# LPC_Female_FMC.net
KiCad netlist of a schematic drawn in Altium Designer
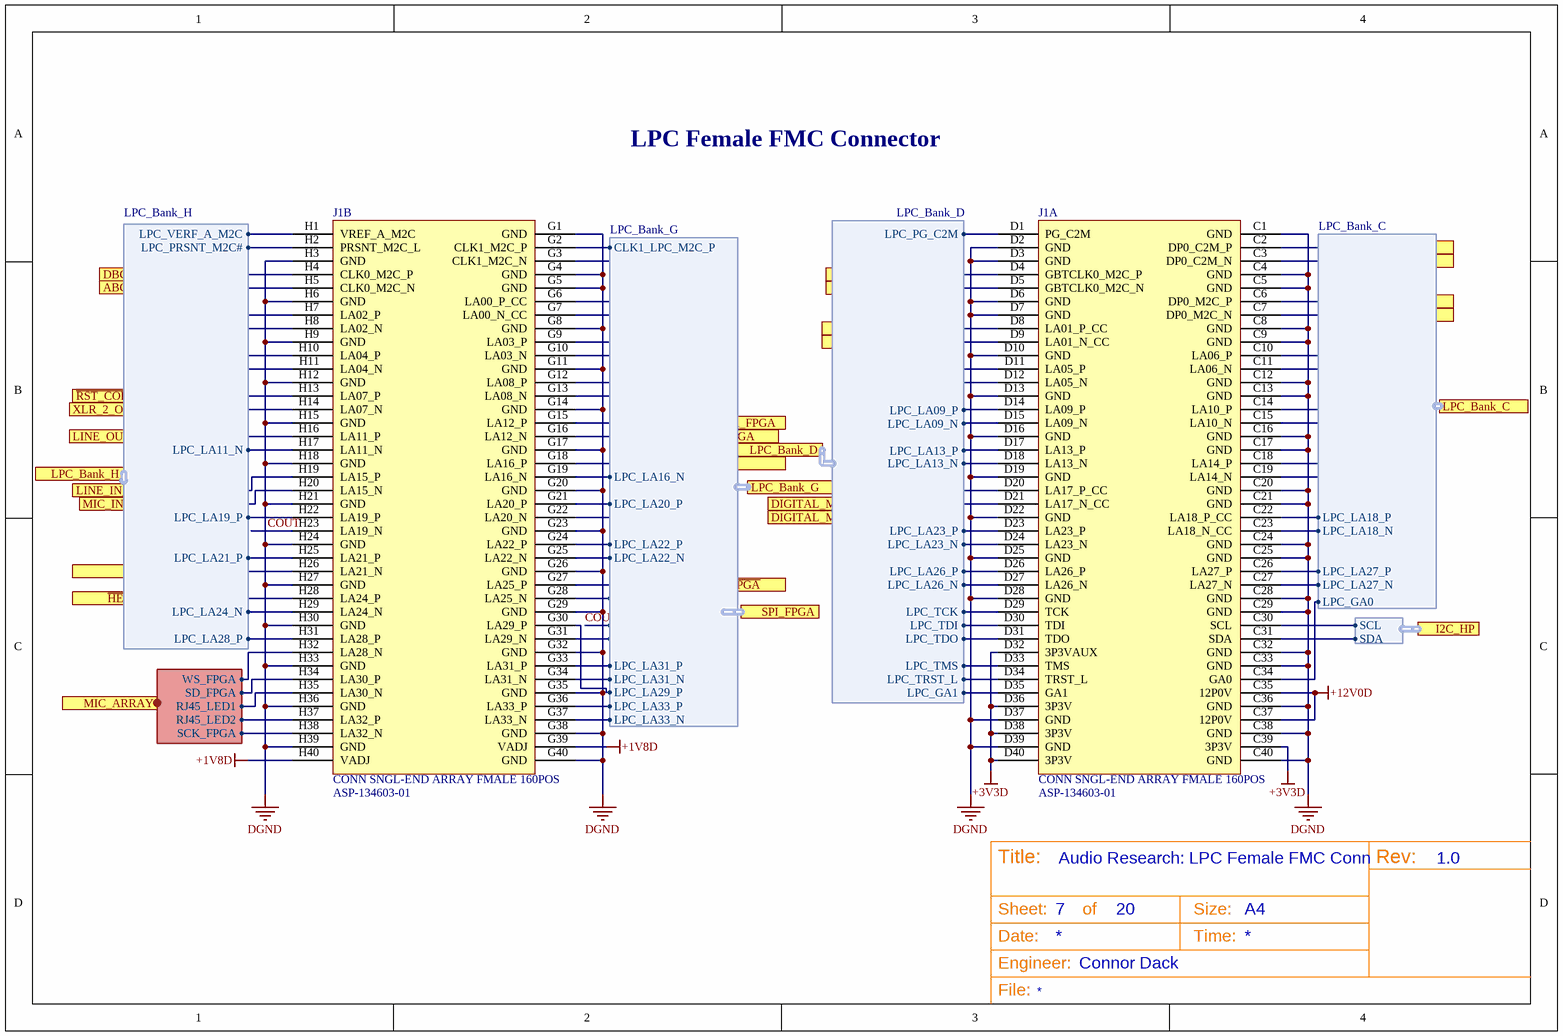
[diagram p0: LPC_Female_FMC.SchDoc]

(export (version "E")
  (design (tool "Eeschema 10.0.6"))
  (components
    (comp (ref "J1")
      (value "CONN SNGL-END ARRAY FMALE 160POS")
      (footprint "ASP-134603-01")
      (description "Low Pin Count Female FPGA Mezzanine Card Connector")
      (fields
        (field (name "MANUFACTURER") "Samtec")
        (field (name "MANUFACTURER PART NUMBER") "ASP-134603-01")
      )
      (libsource (lib "Schematic_Components_CD") (part "ASP-134603-01"))
    )
  )
  (nets
    (net (code "9") (name "+1V8D") (class "Default")
      (node (ref "J1") (pin "G39") (pinfunction "VADJ_G39") (pintype "power_in"))
      (node (ref "J1") (pin "H40") (pinfunction "VADJ_H40") (pintype "power_in"))
    )
    (net (code "10") (name "+3V3D") (class "Default")
      (node (ref "J1") (pin "C39") (pinfunction "3P3V_C39") (pintype "power_in"))
      (node (ref "J1") (pin "D32") (pinfunction "3P3VAUX_D32") (pintype "power_in"))
      (node (ref "J1") (pin "D36") (pinfunction "3P3V_D36") (pintype "power_in"))
      (node (ref "J1") (pin "D38") (pinfunction "3P3V_D38") (pintype "power_in"))
      (node (ref "J1") (pin "D40") (pinfunction "3P3V_D40") (pintype "power_in"))
    )
    (net (code "11") (name "+12V0D") (class "Default")
      (node (ref "J1") (pin "C10") (pinfunction "LA06_P_C10") (pintype "passive"))
      (node (ref "J1") (pin "C11") (pinfunction "LA06_N_C11") (pintype "passive"))
      (node (ref "J1") (pin "C35") (pinfunction "12P0V_C35") (pintype "power_in"))
      (node (ref "J1") (pin "C37") (pinfunction "12P0V_C37") (pintype "power_in"))
      (node (ref "J1") (pin "D11") (pinfunction "LA05_P_D11") (pintype "passive"))
      (node (ref "J1") (pin "D12") (pinfunction "LA05_N_D12") (pintype "passive"))
      (node (ref "J1") (pin "G12") (pinfunction "LA08_P_G12") (pintype "passive"))
      (node (ref "J1") (pin "G13") (pinfunction "LA08_N_G13") (pintype "passive"))
      (node (ref "J1") (pin "H11") (pinfunction "LA04_N_H11") (pintype "passive"))
    )
    (net (code "12") (name "/ABCLK_FPGA") (class "Default")
      (node (ref "J1") (pin "H5") (pinfunction "CLK0_M2C_N_H5") (pintype "passive"))
    )
    (net (code "13") (name "/ALRCLK_FPGA") (class "Default")
      (node (ref "J1") (pin "G22") (pinfunction "LA20_N_G22") (pintype "passive"))
    )
    (net (code "14") (name "/CCLK_FPGA") (class "Default")
      (node (ref "J1") (pin "G31") (pinfunction "LA29_N_G31") (pintype "passive"))
    )
    (net (code "15") (name "/CIN_FPGA") (class "Default")
      (node (ref "J1") (pin "G28") (pinfunction "LA25_N_G28") (pintype "passive"))
    )
    (net (code "16") (name "/CLK1_LPC_M2C_P") (class "Default")
      (node (ref "J1") (pin "G2") (pinfunction "CLK1_M2C_P_G2") (pintype "passive"))
    )
    (net (code "17") (name "/CMD_DIR1") (class "Default")
      (node (ref "J1") (pin "C19") (pinfunction "LA14_N_C19") (pintype "passive"))
    )
    (net (code "18") (name "/CMD_DIR2") (class "Default")
      (node (ref "J1") (pin "C18") (pinfunction "LA14_P_C18") (pintype "passive"))
    )
    (net (code "19") (name "/COUT") (class "Default")
      (node (ref "J1") (pin "H23") (pinfunction "LA19_N_H23") (pintype "passive"))
    )
    (net (code "20") (name "/DATA_DIR1") (class "Default")
      (node (ref "J1") (pin "C15") (pinfunction "LA10_N_C15") (pintype "passive"))
    )
    (net (code "21") (name "/DATA_DIR2") (class "Default")
      (node (ref "J1") (pin "C14") (pinfunction "LA10_P_C14") (pintype "passive"))
    )
    (net (code "22") (name "/DBCLK_FPGA") (class "Default")
      (node (ref "J1") (pin "H4") (pinfunction "CLK0_M2C_P_H4") (pintype "passive"))
    )
    (net (code "23") (name "/DIGITAL_MIC_CLK") (class "Default")
      (node (ref "J1") (pin "D20") (pinfunction "LA17_P_CC_D20") (pintype "passive"))
    )
    (net (code "24") (name "/DIGITAL_MIC_DATA") (class "Default")
      (node (ref "J1") (pin "D21") (pinfunction "LA17_N_CC_D21") (pintype "passive"))
    )
    (net (code "25") (name "/DLRCLK_FPGA") (class "Default")
      (node (ref "J1") (pin "G18") (pinfunction "LA16_P_G18") (pintype "passive"))
    )
    (net (code "26") (name "/HP_OUT_DSDATA_FPGA") (class "Default")
      (node (ref "J1") (pin "G16") (pinfunction "LA12_N_G16") (pintype "passive"))
    )
    (net (code "27") (name "/LED1") (class "Default")
      (node (ref "J1") (pin "C7") (pinfunction "DP0_M2C_N_C7") (pintype "passive"))
    )
    (net (code "28") (name "/LED2") (class "Default")
      (node (ref "J1") (pin "D8") (pinfunction "LA01_P_CC_D8") (pintype "passive"))
    )
    (net (code "29") (name "/LED3") (class "Default")
      (node (ref "J1") (pin "D9") (pinfunction "LA01_N_CC_D9") (pintype "passive"))
    )
    (net (code "30") (name "/LED4") (class "Default")
      (node (ref "J1") (pin "C6") (pinfunction "DP0_M2C_P_C6") (pintype "passive"))
    )
    (net (code "31") (name "/LINE_IN_DSDATA_FPGA") (class "Default")
      (node (ref "J1") (pin "H19") (pinfunction "LA15_P_H19") (pintype "passive"))
    )
    (net (code "32") (name "/LINE_OUT_DSDATA_FPGA") (class "Default")
      (node (ref "J1") (pin "H16") (pinfunction "LA11_P_H16") (pintype "passive"))
    )
    (net (code "34") (name "/LPC_GA0") (class "Default")
      (node (ref "J1") (pin "C34") (pinfunction "GA0_C34") (pintype "passive"))
    )
    (net (code "35") (name "/LPC_GA1") (class "Default")
      (node (ref "J1") (pin "D35") (pinfunction "GA1_D35") (pintype "passive"))
    )
    (net (code "36") (name "/LPC_LA09_N") (class "Default")
      (node (ref "J1") (pin "D15") (pinfunction "LA09_N_D15") (pintype "passive"))
    )
    (net (code "37") (name "/LPC_LA09_P") (class "Default")
      (node (ref "J1") (pin "D14") (pinfunction "LA09_P_D14") (pintype "passive"))
    )
    (net (code "38") (name "/LPC_LA11_N") (class "Default")
      (node (ref "J1") (pin "H17") (pinfunction "LA11_N_H17") (pintype "passive"))
    )
    (net (code "39") (name "/LPC_LA13_N") (class "Default")
      (node (ref "J1") (pin "D18") (pinfunction "LA13_N_D18") (pintype "passive"))
    )
    (net (code "40") (name "/LPC_LA13_P") (class "Default")
      (node (ref "J1") (pin "D17") (pinfunction "LA13_P_D17") (pintype "passive"))
    )
    (net (code "41") (name "/LPC_LA16_N") (class "Default")
      (node (ref "J1") (pin "G19") (pinfunction "LA16_N_G19") (pintype "passive"))
    )
    (net (code "42") (name "/LPC_LA18_N") (class "Default")
      (node (ref "J1") (pin "C23") (pinfunction "LA18_N_CC_C23") (pintype "passive"))
    )
    (net (code "43") (name "/LPC_LA18_P") (class "Default")
      (node (ref "J1") (pin "C22") (pinfunction "LA18_P_CC_C22") (pintype "passive"))
    )
    (net (code "44") (name "/LPC_LA19_P") (class "Default")
      (node (ref "J1") (pin "H22") (pinfunction "LA19_P_H22") (pintype "passive"))
    )
    (net (code "45") (name "/LPC_LA20_P") (class "Default")
      (node (ref "J1") (pin "G21") (pinfunction "LA20_P_G21") (pintype "passive"))
    )
    (net (code "46") (name "/LPC_LA21_P") (class "Default")
      (node (ref "J1") (pin "H25") (pinfunction "LA21_P_H25") (pintype "passive"))
    )
    (net (code "47") (name "/LPC_LA22_N") (class "Default")
      (node (ref "J1") (pin "G25") (pinfunction "LA22_N_G25") (pintype "passive"))
    )
    (net (code "48") (name "/LPC_LA22_P") (class "Default")
      (node (ref "J1") (pin "G24") (pinfunction "LA22_P_G24") (pintype "passive"))
    )
    (net (code "49") (name "/LPC_LA23_N") (class "Default")
      (node (ref "J1") (pin "D24") (pinfunction "LA23_N_D24") (pintype "passive"))
    )
    (net (code "50") (name "/LPC_LA23_P") (class "Default")
      (node (ref "J1") (pin "D23") (pinfunction "LA23_P_D23") (pintype "passive"))
    )
    (net (code "51") (name "/LPC_LA24_N") (class "Default")
      (node (ref "J1") (pin "H29") (pinfunction "LA24_N_H29") (pintype "passive"))
    )
    (net (code "52") (name "/LPC_LA26_N") (class "Default")
      (node (ref "J1") (pin "D27") (pinfunction "LA26_N_D27") (pintype "passive"))
    )
    (net (code "53") (name "/LPC_LA26_P") (class "Default")
      (node (ref "J1") (pin "D26") (pinfunction "LA26_P_D26") (pintype "passive"))
    )
    (net (code "54") (name "/LPC_LA27_N") (class "Default")
      (node (ref "J1") (pin "C27") (pinfunction "LA27_N_C27") (pintype "passive"))
    )
    (net (code "55") (name "/LPC_LA27_P") (class "Default")
      (node (ref "J1") (pin "C26") (pinfunction "LA27_P_C26") (pintype "passive"))
    )
    (net (code "56") (name "/LPC_LA28_P") (class "Default")
      (node (ref "J1") (pin "H31") (pinfunction "LA28_P_H31") (pintype "passive"))
    )
    (net (code "57") (name "/LPC_LA29_P") (class "Default")
      (node (ref "J1") (pin "G30") (pinfunction "LA29_P_G30") (pintype "passive"))
    )
    (net (code "58") (name "/LPC_LA31_N") (class "Default")
      (node (ref "J1") (pin "G34") (pinfunction "LA31_N_G34") (pintype "passive"))
    )
    (net (code "59") (name "/LPC_LA31_P") (class "Default")
      (node (ref "J1") (pin "G33") (pinfunction "LA31_P_G33") (pintype "passive"))
    )
    (net (code "60") (name "/LPC_LA33_N") (class "Default")
      (node (ref "J1") (pin "G37") (pinfunction "LA33_N_G37") (pintype "passive"))
    )
    (net (code "61") (name "/LPC_LA33_P") (class "Default")
      (node (ref "J1") (pin "G36") (pinfunction "LA33_P_G36") (pintype "passive"))
    )
    (net (code "62") (name "/LPC_PG_C2M") (class "Default")
      (node (ref "J1") (pin "D1") (pinfunction "PG_C2M_D1") (pintype "passive"))
    )
    (net (code "63") (name "/LPC_PRSNT_M2C#") (class "Default")
      (node (ref "J1") (pin "H2") (pinfunction "PRSNT_M2C_L_H2") (pintype "passive"))
    )
    (net (code "64") (name "/LPC_TCK") (class "Default")
      (node (ref "J1") (pin "D29") (pinfunction "TCK_D29") (pintype "passive"))
    )
    (net (code "65") (name "/LPC_TDI") (class "Default")
      (node (ref "J1") (pin "D30") (pinfunction "TDI_D30") (pintype "passive"))
    )
    (net (code "66") (name "/LPC_TDO") (class "Default")
      (node (ref "J1") (pin "D31") (pinfunction "TDO_D31") (pintype "passive"))
    )
    (net (code "67") (name "/LPC_TMS") (class "Default")
      (node (ref "J1") (pin "D33") (pinfunction "TMS_D33") (pintype "passive"))
    )
    (net (code "68") (name "/LPC_TRST_L") (class "Default")
      (node (ref "J1") (pin "D34") (pinfunction "TRST_L_D34") (pintype "passive"))
    )
    (net (code "69") (name "/LPC_VERF_A_M2C") (class "Default")
      (node (ref "J1") (pin "H1") (pinfunction "VREF_A_M2C_H1") (pintype "power_in"))
    )
    (net (code "70") (name "/MCLKO_FPGA") (class "Default")
      (node (ref "J1") (pin "G3") (pinfunction "CLK1_M2C_N_G3") (pintype "passive"))
    )
    (net (code "71") (name "/MIC_IN_DSDATA_FPGA") (class "Default")
      (node (ref "J1") (pin "H20") (pinfunction "LA15_N_H20") (pintype "passive"))
    )
    (net (code "72") (name "/MMC0_CLK") (class "Default")
      (node (ref "J1") (pin "G7") (pinfunction "LA00_N_CC_G7") (pintype "passive"))
    )
    (net (code "73") (name "/MMC0_CMD") (class "Default")
      (node (ref "J1") (pin "G9") (pinfunction "LA03_P_G9") (pintype "passive"))
    )
    (net (code "74") (name "/MMC0_DAT0") (class "Default")
      (node (ref "J1") (pin "G10") (pinfunction "LA03_N_G10") (pintype "passive"))
    )
    (net (code "75") (name "/MMC0_DAT1") (class "Default")
      (node (ref "J1") (pin "H10") (pinfunction "LA04_P_H10") (pintype "passive"))
    )
    (net (code "76") (name "/MMC0_DAT2") (class "Default")
      (node (ref "J1") (pin "H7") (pinfunction "LA02_P_H7") (pintype "passive"))
    )
    (net (code "77") (name "/MMC0_DAT3") (class "Default")
      (node (ref "J1") (pin "H8") (pinfunction "LA02_N_H8") (pintype "passive"))
    )
    (net (code "78") (name "/MMC0_SDCD") (class "Default")
      (node (ref "J1") (pin "G6") (pinfunction "LA00_P_CC_G6") (pintype "passive"))
    )
    (net (code "79") (name "/RJ45_LED1") (class "Default")
      (node (ref "J1") (pin "H35") (pinfunction "LA30_N_H35") (pintype "passive"))
    )
    (net (code "80") (name "/RJ45_LED2") (class "Default")
      (node (ref "J1") (pin "H37") (pinfunction "LA32_P_H37") (pintype "passive"))
    )
    (net (code "81") (name "/SCK_FPGA") (class "Default")
      (node (ref "J1") (pin "H38") (pinfunction "LA32_N_H38") (pintype "passive"))
    )
    (net (code "82") (name "/SCL") (class "Default")
      (node (ref "J1") (pin "C30") (pinfunction "SCL_C30") (pintype "passive"))
    )
    (net (code "83") (name "/SDA") (class "Default")
      (node (ref "J1") (pin "C31") (pinfunction "SDA_C31") (pintype "passive"))
    )
    (net (code "84") (name "/SD_FPGA") (class "Default")
      (node (ref "J1") (pin "H34") (pinfunction "LA30_P_H34") (pintype "passive"))
    )
    (net (code "85") (name "/SW1") (class "Default")
      (node (ref "J1") (pin "C2") (pinfunction "DP0_C2M_P_C2") (pintype "passive"))
    )
    (net (code "86") (name "/SW2") (class "Default")
      (node (ref "J1") (pin "C3") (pinfunction "DP0_C2M_N_C3") (pintype "passive"))
    )
    (net (code "87") (name "/SW3") (class "Default")
      (node (ref "J1") (pin "D4") (pinfunction "GBTCLK0_M2C_P_D4") (pintype "passive"))
    )
    (net (code "88") (name "/SW4") (class "Default")
      (node (ref "J1") (pin "D5") (pinfunction "GBTCLK0_M2C_N_D5") (pintype "passive"))
    )
    (net (code "89") (name "/WS_FPGA") (class "Default")
      (node (ref "J1") (pin "H32") (pinfunction "LA28_N_H32") (pintype "passive"))
    )
    (net (code "90") (name "/XLR_1_OUT_DSDATA_FPGA") (class "Default")
      (node (ref "J1") (pin "G15") (pinfunction "LA12_P_G15") (pintype "passive"))
    )
    (net (code "91") (name "/XLR_2_OUT_DSDATA_FPGA") (class "Default")
      (node (ref "J1") (pin "H14") (pinfunction "LA07_N_H14") (pintype "passive"))
    )
    (net (code "98") (name "/~{CS_AUDIO_CODEC_FPGA}") (class "Default")
      (node (ref "J1") (pin "G27") (pinfunction "LA25_P_G27") (pintype "passive"))
    )
    (net (code "99") (name "/~{CS_PRE_AMP_FPGA}") (class "Default")
      (node (ref "J1") (pin "H26") (pinfunction "LA21_N_H26") (pintype "passive"))
    )
    (net (code "100") (name "/~{HEADPHONE_SD_FPGA}") (class "Default")
      (node (ref "J1") (pin "H28") (pinfunction "LA24_P_H28") (pintype "passive"))
    )
    (net (code "101") (name "/~{RST_CODEC_FPGA}") (class "Default")
      (node (ref "J1") (pin "H13") (pinfunction "LA07_P_H13") (pintype "passive"))
    )
    (net (code "102") (name "DGND") (class "Default")
      (node (ref "J1") (pin "C1") (pinfunction "GND_C1") (pintype "power_in"))
      (node (ref "J1") (pin "C12") (pinfunction "GND_C12") (pintype "power_in"))
      (node (ref "J1") (pin "C13") (pinfunction "GND_C13") (pintype "power_in"))
      (node (ref "J1") (pin "C16") (pinfunction "GND_C16") (pintype "power_in"))
      (node (ref "J1") (pin "C17") (pinfunction "GND_C17") (pintype "power_in"))
      (node (ref "J1") (pin "C20") (pinfunction "GND_C20") (pintype "power_in"))
      (node (ref "J1") (pin "C21") (pinfunction "GND_C21") (pintype "power_in"))
      (node (ref "J1") (pin "C24") (pinfunction "GND_C24") (pintype "power_in"))
      (node (ref "J1") (pin "C25") (pinfunction "GND_C25") (pintype "power_in"))
      (node (ref "J1") (pin "C28") (pinfunction "GND_C28") (pintype "power_in"))
      (node (ref "J1") (pin "C29") (pinfunction "GND_C29") (pintype "power_in"))
      (node (ref "J1") (pin "C32") (pinfunction "GND_C32") (pintype "power_in"))
      (node (ref "J1") (pin "C33") (pinfunction "GND_C33") (pintype "power_in"))
      (node (ref "J1") (pin "C36") (pinfunction "GND_C36") (pintype "power_in"))
      (node (ref "J1") (pin "C38") (pinfunction "GND_C38") (pintype "power_in"))
      (node (ref "J1") (pin "C4") (pinfunction "GND_C4") (pintype "power_in"))
      (node (ref "J1") (pin "C40") (pinfunction "GND_C40") (pintype "power_in"))
      (node (ref "J1") (pin "C5") (pinfunction "GND_C5") (pintype "power_in"))
      (node (ref "J1") (pin "C8") (pinfunction "GND_C8") (pintype "power_in"))
      (node (ref "J1") (pin "C9") (pinfunction "GND_C9") (pintype "power_in"))
      (node (ref "J1") (pin "D10") (pinfunction "GND_D10") (pintype "power_in"))
      (node (ref "J1") (pin "D13") (pinfunction "GND_D13") (pintype "power_in"))
      (node (ref "J1") (pin "D16") (pinfunction "GND_D16") (pintype "power_in"))
      (node (ref "J1") (pin "D19") (pinfunction "GND_D19") (pintype "power_in"))
      (node (ref "J1") (pin "D2") (pinfunction "GND_D2") (pintype "power_in"))
      (node (ref "J1") (pin "D22") (pinfunction "GND_D22") (pintype "power_in"))
      (node (ref "J1") (pin "D25") (pinfunction "GND_D25") (pintype "power_in"))
      (node (ref "J1") (pin "D28") (pinfunction "GND_D28") (pintype "power_in"))
      (node (ref "J1") (pin "D3") (pinfunction "GND_D3") (pintype "power_in"))
      (node (ref "J1") (pin "D37") (pinfunction "GND_D37") (pintype "power_in"))
      (node (ref "J1") (pin "D39") (pinfunction "GND_D39") (pintype "power_in"))
      (node (ref "J1") (pin "D6") (pinfunction "GND_D6") (pintype "power_in"))
      (node (ref "J1") (pin "D7") (pinfunction "GND_D7") (pintype "power_in"))
      (node (ref "J1") (pin "G1") (pinfunction "GND_G1") (pintype "power_in"))
      (node (ref "J1") (pin "G11") (pinfunction "GND_G11") (pintype "power_in"))
      (node (ref "J1") (pin "G14") (pinfunction "GND_G14") (pintype "power_in"))
      (node (ref "J1") (pin "G17") (pinfunction "GND_G17") (pintype "power_in"))
      (node (ref "J1") (pin "G20") (pinfunction "GND_G20") (pintype "power_in"))
      (node (ref "J1") (pin "G23") (pinfunction "GND_G23") (pintype "power_in"))
      (node (ref "J1") (pin "G26") (pinfunction "GND_G26") (pintype "power_in"))
      (node (ref "J1") (pin "G29") (pinfunction "GND_G29") (pintype "power_in"))
      (node (ref "J1") (pin "G32") (pinfunction "GND_G32") (pintype "power_in"))
      (node (ref "J1") (pin "G35") (pinfunction "GND_G35") (pintype "power_in"))
      (node (ref "J1") (pin "G38") (pinfunction "GND_G38") (pintype "power_in"))
      (node (ref "J1") (pin "G4") (pinfunction "GND_G4") (pintype "power_in"))
      (node (ref "J1") (pin "G40") (pinfunction "GND_G40") (pintype "power_in"))
      (node (ref "J1") (pin "G5") (pinfunction "GND_G5") (pintype "power_in"))
      (node (ref "J1") (pin "G8") (pinfunction "GND_G8") (pintype "power_in"))
      (node (ref "J1") (pin "H12") (pinfunction "GND_H12") (pintype "power_in"))
      (node (ref "J1") (pin "H15") (pinfunction "GND_H15") (pintype "power_in"))
      (node (ref "J1") (pin "H18") (pinfunction "GND_H18") (pintype "power_in"))
      (node (ref "J1") (pin "H21") (pinfunction "GND_H21") (pintype "power_in"))
      (node (ref "J1") (pin "H24") (pinfunction "GND_H24") (pintype "power_in"))
      (node (ref "J1") (pin "H27") (pinfunction "GND_H27") (pintype "power_in"))
      (node (ref "J1") (pin "H3") (pinfunction "GND_H3") (pintype "power_in"))
      (node (ref "J1") (pin "H30") (pinfunction "GND_H30") (pintype "power_in"))
      (node (ref "J1") (pin "H33") (pinfunction "GND_H33") (pintype "power_in"))
      (node (ref "J1") (pin "H36") (pinfunction "GND_H36") (pintype "power_in"))
      (node (ref "J1") (pin "H39") (pinfunction "GND_H39") (pintype "power_in"))
      (node (ref "J1") (pin "H6") (pinfunction "GND_H6") (pintype "power_in"))
      (node (ref "J1") (pin "H9") (pinfunction "GND_H9") (pintype "power_in"))
    )
  )
)
